# LT3652_PCB.net
KiCad netlist of a schematic drawn in EAGLE
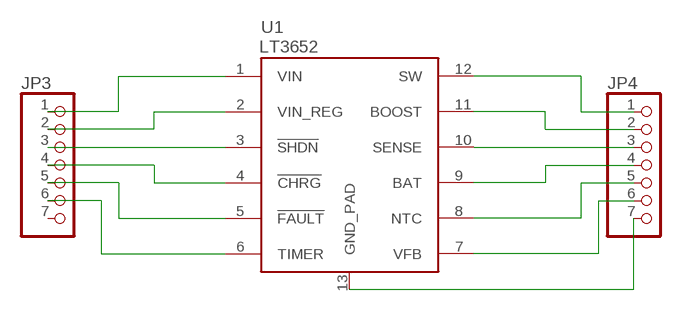
[diagram p0: schematic, sheet 1]

(export (version "E")
  (design (tool "Eeschema 10.0.6"))
  (components
    (comp (ref "JP3")
      (value "PINHD-1X7")
      (footprint "eagle-import:1X07")
      (libsource (lib "eagle-import") (part "PINHD-1X7"))
    )
    (comp (ref "JP4")
      (value "PINHD-1X7")
      (footprint "eagle-import:1X07")
      (libsource (lib "eagle-import") (part "PINHD-1X7"))
    )
    (comp (ref "U1")
      (value "LT3652")
      (footprint "eagle-import:MSOP-12_GND")
      (libsource (lib "eagle-import") (part "LT3652"))
    )
  )
  (nets
    (net (code "1") (name "Net-(U1-BAT)") (class "Default")
      (node (ref "JP4") (pin "4") (pinfunction "4_4") (pintype "passive"))
      (node (ref "U1") (pin "9") (pinfunction "BAT_9") (pintype "bidirectional"))
    )
    (net (code "2") (name "Net-(U1-BOOST)") (class "Default")
      (node (ref "JP4") (pin "2") (pinfunction "2_2") (pintype "passive"))
      (node (ref "U1") (pin "11") (pinfunction "BOOST_11") (pintype "bidirectional"))
    )
    (net (code "3") (name "Net-(U1-GND_PAD)") (class "Default")
      (node (ref "JP4") (pin "7") (pinfunction "7_7") (pintype "passive"))
      (node (ref "U1") (pin "13") (pinfunction "GND_PAD_13") (pintype "bidirectional"))
    )
    (net (code "4") (name "Net-(U1-NTC)") (class "Default")
      (node (ref "JP4") (pin "5") (pinfunction "5_5") (pintype "passive"))
      (node (ref "U1") (pin "8") (pinfunction "NTC_8") (pintype "bidirectional"))
    )
    (net (code "5") (name "Net-(U1-SENSE)") (class "Default")
      (node (ref "JP4") (pin "3") (pinfunction "3_3") (pintype "passive"))
      (node (ref "U1") (pin "10") (pinfunction "SENSE_10") (pintype "bidirectional"))
    )
    (net (code "6") (name "Net-(U1-SW)") (class "Default")
      (node (ref "JP4") (pin "1") (pinfunction "1_1") (pintype "passive"))
      (node (ref "U1") (pin "12") (pinfunction "SW_12") (pintype "bidirectional"))
    )
    (net (code "7") (name "Net-(U1-TIMER)") (class "Default")
      (node (ref "JP3") (pin "6") (pinfunction "6_6") (pintype "passive"))
      (node (ref "U1") (pin "6") (pinfunction "TIMER_6") (pintype "bidirectional"))
    )
    (net (code "8") (name "Net-(U1-VFB)") (class "Default")
      (node (ref "JP4") (pin "6") (pinfunction "6_6") (pintype "passive"))
      (node (ref "U1") (pin "7") (pinfunction "VFB_7") (pintype "bidirectional"))
    )
    (net (code "9") (name "Net-(U1-VIN)") (class "Default")
      (node (ref "JP3") (pin "1") (pinfunction "1_1") (pintype "passive"))
      (node (ref "U1") (pin "1") (pinfunction "VIN_1") (pintype "bidirectional"))
    )
    (net (code "10") (name "Net-(U1-VIN_REG)") (class "Default")
      (node (ref "JP3") (pin "2") (pinfunction "2_2") (pintype "passive"))
      (node (ref "U1") (pin "2") (pinfunction "VIN_REG_2") (pintype "bidirectional"))
    )
    (net (code "11") (name "Net-(U1-~{CHRG})") (class "Default")
      (node (ref "JP3") (pin "4") (pinfunction "4_4") (pintype "passive"))
      (node (ref "U1") (pin "4") (pinfunction "~{CHRG}_4") (pintype "bidirectional"))
    )
    (net (code "12") (name "Net-(U1-~{FAULT})") (class "Default")
      (node (ref "JP3") (pin "5") (pinfunction "5_5") (pintype "passive"))
      (node (ref "U1") (pin "5") (pinfunction "~{FAULT}_5") (pintype "bidirectional"))
    )
    (net (code "13") (name "Net-(U1-~{SHDN})") (class "Default")
      (node (ref "JP3") (pin "3") (pinfunction "3_3") (pintype "passive"))
      (node (ref "U1") (pin "3") (pinfunction "~{SHDN}_3") (pintype "bidirectional"))
    )
    (net (code "14") (name "unconnected-(JP3-Pad7)") (class "Default")
      (node (ref "JP3") (pin "7") (pinfunction "7_7") (pintype "passive"))
    )
  )
)
